# US_AB_SC.net
KiCad netlist of a schematic drawn in Altium Designer
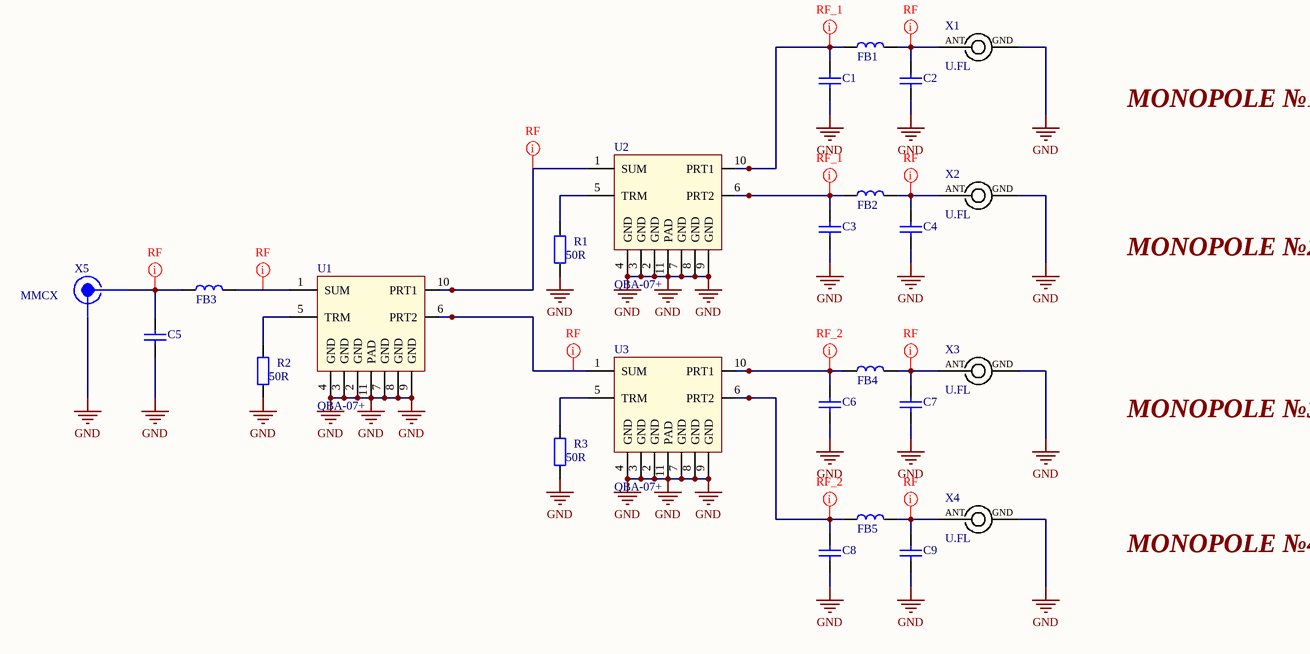
[diagram p0: US_AB_SC.SchDoc]

(export (version "E")
  (design (tool "Eeschema 10.0.6"))
  (components
    (comp (ref "C1")
      (value "100n")
      (footprint "C0603_IPC_MD")
      (fields
        (field (name "MANUFACTURER") "Samsung Electro-Mechanics")
        (field (name "MANUFACTURER PART NUMBER") "CL10B104KO8NNNC")
        (field (name "VOLTAGE") "16V")
      )
      (libsource (lib "alfasat_lib") (part "CL10B104KO8NNNC"))
    )
    (comp (ref "C2")
      (value "100n")
      (footprint "C0603_IPC_MD")
      (fields
        (field (name "MANUFACTURER") "Samsung Electro-Mechanics")
        (field (name "MANUFACTURER PART NUMBER") "CL10B104KO8NNNC")
        (field (name "VOLTAGE") "16V")
      )
      (libsource (lib "alfasat_lib") (part "CL10B104KO8NNNC"))
    )
    (comp (ref "C3")
      (value "100n")
      (footprint "C0603_IPC_MD")
      (fields
        (field (name "MANUFACTURER") "Samsung Electro-Mechanics")
        (field (name "MANUFACTURER PART NUMBER") "CL10B104KO8NNNC")
        (field (name "VOLTAGE") "16V")
      )
      (libsource (lib "alfasat_lib") (part "CL10B104KO8NNNC"))
    )
    (comp (ref "C4")
      (value "100n")
      (footprint "C0603_IPC_MD")
      (fields
        (field (name "MANUFACTURER") "Samsung Electro-Mechanics")
        (field (name "MANUFACTURER PART NUMBER") "CL10B104KO8NNNC")
        (field (name "VOLTAGE") "16V")
      )
      (libsource (lib "alfasat_lib") (part "CL10B104KO8NNNC"))
    )
    (comp (ref "C5")
      (value "100n")
      (footprint "C0603_IPC_MD")
      (fields
        (field (name "MANUFACTURER") "Samsung Electro-Mechanics")
        (field (name "MANUFACTURER PART NUMBER") "CL10B104KO8NNNC")
        (field (name "VOLTAGE") "16V")
      )
      (libsource (lib "alfasat_lib") (part "CL10B104KO8NNNC"))
    )
    (comp (ref "C6")
      (value "100n")
      (footprint "C0603_IPC_MD")
      (fields
        (field (name "MANUFACTURER") "Samsung Electro-Mechanics")
        (field (name "MANUFACTURER PART NUMBER") "CL10B104KO8NNNC")
        (field (name "VOLTAGE") "16V")
      )
      (libsource (lib "alfasat_lib") (part "CL10B104KO8NNNC"))
    )
    (comp (ref "C7")
      (value "100n")
      (footprint "C0603_IPC_MD")
      (fields
        (field (name "MANUFACTURER") "Samsung Electro-Mechanics")
        (field (name "MANUFACTURER PART NUMBER") "CL10B104KO8NNNC")
        (field (name "VOLTAGE") "16V")
      )
      (libsource (lib "alfasat_lib") (part "CL10B104KO8NNNC"))
    )
    (comp (ref "C8")
      (value "100n")
      (footprint "C0603_IPC_MD")
      (fields
        (field (name "MANUFACTURER") "Samsung Electro-Mechanics")
        (field (name "MANUFACTURER PART NUMBER") "CL10B104KO8NNNC")
        (field (name "VOLTAGE") "16V")
      )
      (libsource (lib "alfasat_lib") (part "CL10B104KO8NNNC"))
    )
    (comp (ref "C9")
      (value "100n")
      (footprint "C0603_IPC_MD")
      (fields
        (field (name "MANUFACTURER") "Samsung Electro-Mechanics")
        (field (name "MANUFACTURER PART NUMBER") "CL10B104KO8NNNC")
        (field (name "VOLTAGE") "16V")
      )
      (libsource (lib "alfasat_lib") (part "CL10B104KO8NNNC"))
    )
    (comp (ref "FB1")
      (value "MH1608-601Y")
      (footprint "L0603_IPC_LD")
      (description "FERRITE BEAD 600R@100MHz 0603 for Power Line, 1000mA")
      (fields (field (name "MANUFACTURER") "Bourns Inc."))
      (libsource (lib "alfasat_lib") (part "MH1608-601Y"))
    )
    (comp (ref "FB2")
      (value "MH1608-601Y")
      (footprint "L0603_IPC_LD")
      (description "FERRITE BEAD 600R@100MHz 0603 for Power Line, 1000mA")
      (fields (field (name "MANUFACTURER") "Bourns Inc."))
      (libsource (lib "alfasat_lib") (part "MH1608-601Y"))
    )
    (comp (ref "FB3")
      (value "MH1608-601Y")
      (footprint "L0603_IPC_LD")
      (description "FERRITE BEAD 600R@100MHz 0603 for Power Line, 1000mA")
      (fields (field (name "MANUFACTURER") "Bourns Inc."))
      (libsource (lib "alfasat_lib") (part "MH1608-601Y"))
    )
    (comp (ref "FB4")
      (value "MH1608-601Y")
      (footprint "L0603_IPC_LD")
      (description "FERRITE BEAD 600R@100MHz 0603 for Power Line, 1000mA")
      (fields (field (name "MANUFACTURER") "Bourns Inc."))
      (libsource (lib "alfasat_lib") (part "MH1608-601Y"))
    )
    (comp (ref "FB5")
      (value "MH1608-601Y")
      (footprint "L0603_IPC_LD")
      (description "FERRITE BEAD 600R@100MHz 0603 for Power Line, 1000mA")
      (fields (field (name "MANUFACTURER") "Bourns Inc."))
      (libsource (lib "alfasat_lib") (part "MH1608-601Y"))
    )
    (comp (ref "R1")
      (value "50R")
      (footprint "R0603_IPC_MD")
      (description "RES SMD 0 OHM JUMPER 1/10W 0603")
      (fields
        (field (name "MANUFACTURER") "Bourns Inc.")
        (field (name "MANUFACTURER PART NUMBER") "CR0603-J/-000ELF")
      )
      (libsource (lib "alfasat_lib") (part "CR0603-J/-000ELF"))
    )
    (comp (ref "R2")
      (value "50R")
      (footprint "R0603_IPC_MD")
      (description "RES SMD 0 OHM JUMPER 1/10W 0603")
      (fields
        (field (name "MANUFACTURER") "Bourns Inc.")
        (field (name "MANUFACTURER PART NUMBER") "CR0603-J/-000ELF")
      )
      (libsource (lib "alfasat_lib") (part "CR0603-J/-000ELF"))
    )
    (comp (ref "R3")
      (value "50R")
      (footprint "R0603_IPC_MD")
      (description "RES SMD 0 OHM JUMPER 1/10W 0603")
      (fields
        (field (name "MANUFACTURER") "Bourns Inc.")
        (field (name "MANUFACTURER PART NUMBER") "CR0603-J/-000ELF")
      )
      (libsource (lib "alfasat_lib") (part "CR0603-J/-000ELF"))
    )
    (comp (ref "U1")
      (value "QBA-07+")
      (footprint "QBA-07+")
      (description "Power Splitter/Combiner 2 Way-90° 50Ω 340 to 680 MHz")
      (fields (field (name "MANUFACTURER") "Mini-Circuits®"))
      (libsource (lib "alfasat_lib_eps") (part "QBA-07+"))
    )
    (comp (ref "U2")
      (value "QBA-07+")
      (footprint "QBA-07+")
      (description "Power Splitter/Combiner 2 Way-90° 50Ω 340 to 680 MHz")
      (fields (field (name "MANUFACTURER") "Mini-Circuits®"))
      (libsource (lib "alfasat_lib_eps") (part "QBA-07+"))
    )
    (comp (ref "U3")
      (value "QBA-07+")
      (footprint "QBA-07+")
      (description "Power Splitter/Combiner 2 Way-90° 50Ω 340 to 680 MHz")
      (fields (field (name "MANUFACTURER") "Mini-Circuits®"))
      (libsource (lib "alfasat_lib_eps") (part "QBA-07+"))
    )
    (comp (ref "X1")
      (value "U.FL")
      (footprint "U.FL")
      (description "SMA slot")
      (libsource (lib "Connectors") (part "U.FL"))
    )
    (comp (ref "X2")
      (value "U.FL")
      (footprint "U.FL")
      (description "SMA slot")
      (libsource (lib "Connectors") (part "U.FL"))
    )
    (comp (ref "X3")
      (value "U.FL")
      (footprint "U.FL")
      (description "SMA slot")
      (libsource (lib "Connectors") (part "U.FL"))
    )
    (comp (ref "X4")
      (value "U.FL")
      (footprint "U.FL")
      (description "SMA slot")
      (libsource (lib "Connectors") (part "U.FL"))
    )
    (comp (ref "X5")
      (value "MMCX")
      (footprint "MMCX_EDGE")
      (description "MMCX PCB EDGE CONN")
      (fields (field (name "MANUFACTURER") "China"))
      (libsource (lib "alfasat_parts_lib") (part "MMCX"))
    )
  )
  (nets
    (net (code "1") (name "GND") (class "Default")
      (node (ref "C1") (pin "1") (pinfunction "1_1") (pintype "passive"))
      (node (ref "C2") (pin "1") (pinfunction "1_1") (pintype "passive"))
      (node (ref "C3") (pin "1") (pinfunction "1_1") (pintype "passive"))
      (node (ref "C4") (pin "1") (pinfunction "1_1") (pintype "passive"))
      (node (ref "C5") (pin "1") (pinfunction "1_1") (pintype "passive"))
      (node (ref "C6") (pin "1") (pinfunction "1_1") (pintype "passive"))
      (node (ref "C7") (pin "1") (pinfunction "1_1") (pintype "passive"))
      (node (ref "C8") (pin "1") (pinfunction "1_1") (pintype "passive"))
      (node (ref "C9") (pin "1") (pinfunction "1_1") (pintype "passive"))
      (node (ref "R1") (pin "1") (pinfunction "1_1") (pintype "passive"))
      (node (ref "R2") (pin "1") (pinfunction "1_1") (pintype "passive"))
      (node (ref "R3") (pin "1") (pinfunction "1_1") (pintype "passive"))
      (node (ref "U1") (pin "11") (pinfunction "PAD_11") (pintype "passive"))
      (node (ref "U1") (pin "2") (pinfunction "GND_2") (pintype "passive"))
      (node (ref "U1") (pin "3") (pinfunction "GND_3") (pintype "passive"))
      (node (ref "U1") (pin "4") (pinfunction "GND_4") (pintype "passive"))
      (node (ref "U1") (pin "7") (pinfunction "GND_7") (pintype "passive"))
      (node (ref "U1") (pin "8") (pinfunction "GND_8") (pintype "passive"))
      (node (ref "U1") (pin "9") (pinfunction "GND_9") (pintype "passive"))
      (node (ref "U2") (pin "11") (pinfunction "PAD_11") (pintype "passive"))
      (node (ref "U2") (pin "2") (pinfunction "GND_2") (pintype "passive"))
      (node (ref "U2") (pin "3") (pinfunction "GND_3") (pintype "passive"))
      (node (ref "U2") (pin "4") (pinfunction "GND_4") (pintype "passive"))
      (node (ref "U2") (pin "7") (pinfunction "GND_7") (pintype "passive"))
      (node (ref "U2") (pin "8") (pinfunction "GND_8") (pintype "passive"))
      (node (ref "U2") (pin "9") (pinfunction "GND_9") (pintype "passive"))
      (node (ref "U3") (pin "11") (pinfunction "PAD_11") (pintype "passive"))
      (node (ref "U3") (pin "2") (pinfunction "GND_2") (pintype "passive"))
      (node (ref "U3") (pin "3") (pinfunction "GND_3") (pintype "passive"))
      (node (ref "U3") (pin "4") (pinfunction "GND_4") (pintype "passive"))
      (node (ref "U3") (pin "7") (pinfunction "GND_7") (pintype "passive"))
      (node (ref "U3") (pin "8") (pinfunction "GND_8") (pintype "passive"))
      (node (ref "U3") (pin "9") (pinfunction "GND_9") (pintype "passive"))
      (node (ref "X1") (pin "1") (pinfunction "1_1") (pintype "passive"))
      (node (ref "X2") (pin "1") (pinfunction "1_1") (pintype "passive"))
      (node (ref "X3") (pin "1") (pinfunction "1_1") (pintype "passive"))
      (node (ref "X4") (pin "1") (pinfunction "1_1") (pintype "passive"))
      (node (ref "X5") (pin "1") (pinfunction "1_1") (pintype "passive"))
    )
    (net (code "2") (name "Net-(C2-Pad2)") (class "Default")
      (node (ref "C2") (pin "2") (pinfunction "2_2") (pintype "passive"))
      (node (ref "FB1") (pin "2") (pinfunction "2_2") (pintype "passive"))
      (node (ref "X1") (pin "2") (pinfunction "2_2") (pintype "passive"))
    )
    (net (code "3") (name "Net-(C4-Pad2)") (class "Default")
      (node (ref "C4") (pin "2") (pinfunction "2_2") (pintype "passive"))
      (node (ref "FB2") (pin "2") (pinfunction "2_2") (pintype "passive"))
      (node (ref "X2") (pin "2") (pinfunction "2_2") (pintype "passive"))
    )
    (net (code "4") (name "Net-(C5-Pad2)") (class "Default")
      (node (ref "C5") (pin "2") (pinfunction "2_2") (pintype "passive"))
      (node (ref "FB3") (pin "1") (pinfunction "1_1") (pintype "passive"))
      (node (ref "X5") (pin "2") (pinfunction "2_2") (pintype "passive"))
    )
    (net (code "5") (name "Net-(C7-Pad2)") (class "Default")
      (node (ref "C7") (pin "2") (pinfunction "2_2") (pintype "passive"))
      (node (ref "FB4") (pin "2") (pinfunction "2_2") (pintype "passive"))
      (node (ref "X3") (pin "2") (pinfunction "2_2") (pintype "passive"))
    )
    (net (code "6") (name "Net-(C9-Pad2)") (class "Default")
      (node (ref "C9") (pin "2") (pinfunction "2_2") (pintype "passive"))
      (node (ref "FB5") (pin "2") (pinfunction "2_2") (pintype "passive"))
      (node (ref "X4") (pin "2") (pinfunction "2_2") (pintype "passive"))
    )
    (net (code "7") (name "Net-(U1-PRT1)") (class "Default")
      (node (ref "U1") (pin "10") (pinfunction "PRT1_10") (pintype "passive"))
      (node (ref "U2") (pin "1") (pinfunction "SUM_1") (pintype "passive"))
    )
    (net (code "8") (name "Net-(U1-PRT2)") (class "Default")
      (node (ref "U1") (pin "6") (pinfunction "PRT2_6") (pintype "passive"))
      (node (ref "U3") (pin "1") (pinfunction "SUM_1") (pintype "passive"))
    )
    (net (code "9") (name "Net-(U1-SUM)") (class "Default")
      (node (ref "FB3") (pin "2") (pinfunction "2_2") (pintype "passive"))
      (node (ref "U1") (pin "1") (pinfunction "SUM_1") (pintype "passive"))
    )
    (net (code "10") (name "Net-(U1-TRM)") (class "Default")
      (node (ref "R2") (pin "2") (pinfunction "2_2") (pintype "passive"))
      (node (ref "U1") (pin "5") (pinfunction "TRM_5") (pintype "passive"))
    )
    (net (code "11") (name "Net-(U2-PRT1)") (class "Default")
      (node (ref "C1") (pin "2") (pinfunction "2_2") (pintype "passive"))
      (node (ref "FB1") (pin "1") (pinfunction "1_1") (pintype "passive"))
      (node (ref "U2") (pin "10") (pinfunction "PRT1_10") (pintype "passive"))
    )
    (net (code "12") (name "Net-(U2-PRT2)") (class "Default")
      (node (ref "C3") (pin "2") (pinfunction "2_2") (pintype "passive"))
      (node (ref "FB2") (pin "1") (pinfunction "1_1") (pintype "passive"))
      (node (ref "U2") (pin "6") (pinfunction "PRT2_6") (pintype "passive"))
    )
    (net (code "13") (name "Net-(U2-TRM)") (class "Default")
      (node (ref "R1") (pin "2") (pinfunction "2_2") (pintype "passive"))
      (node (ref "U2") (pin "5") (pinfunction "TRM_5") (pintype "passive"))
    )
    (net (code "14") (name "Net-(U3-PRT1)") (class "Default")
      (node (ref "C6") (pin "2") (pinfunction "2_2") (pintype "passive"))
      (node (ref "FB4") (pin "1") (pinfunction "1_1") (pintype "passive"))
      (node (ref "U3") (pin "10") (pinfunction "PRT1_10") (pintype "passive"))
    )
    (net (code "15") (name "Net-(U3-PRT2)") (class "Default")
      (node (ref "C8") (pin "2") (pinfunction "2_2") (pintype "passive"))
      (node (ref "FB5") (pin "1") (pinfunction "1_1") (pintype "passive"))
      (node (ref "U3") (pin "6") (pinfunction "PRT2_6") (pintype "passive"))
    )
    (net (code "16") (name "Net-(U3-TRM)") (class "Default")
      (node (ref "R3") (pin "2") (pinfunction "2_2") (pintype "passive"))
      (node (ref "U3") (pin "5") (pinfunction "TRM_5") (pintype "passive"))
    )
  )
)
